# STM32VET6.net
KiCad netlist of a schematic drawn in Altium Designer
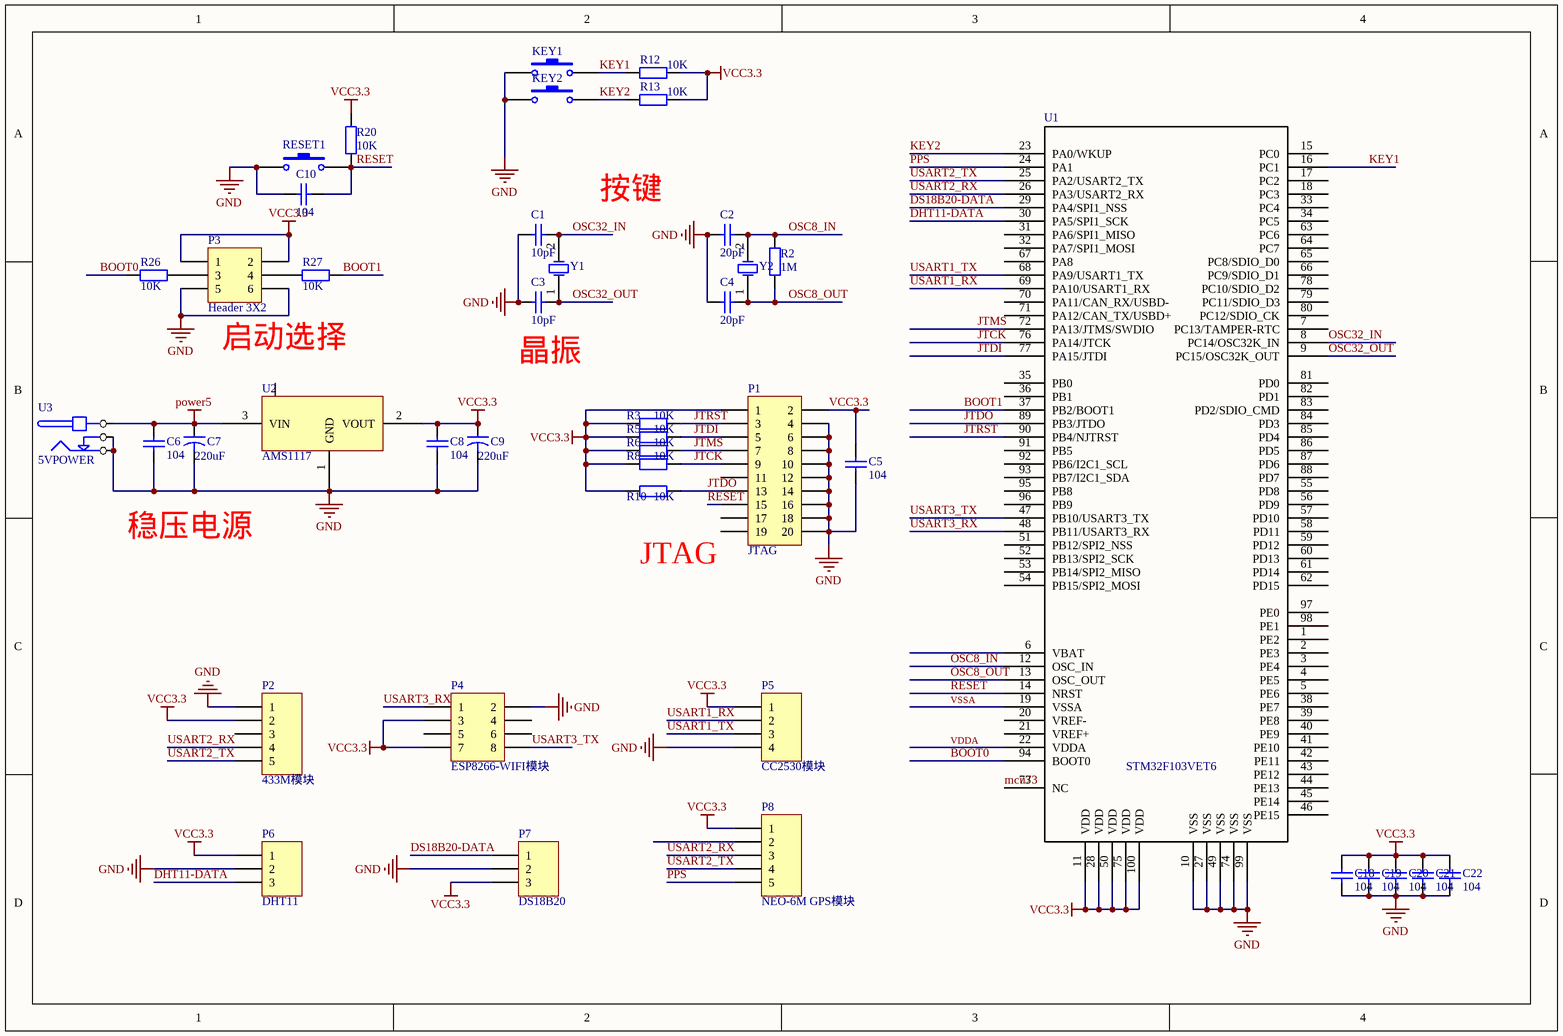
[diagram p0: STM32VET6.SchDoc]

(export (version "E")
  (design (tool "Eeschema 10.0.6"))
  (components
    (comp (ref "C1")
      (value "10pF")
      (footprint "0805")
      (description "Capacitor")
      (fields (field (name "Comment") "Cap") (field (name "PUBLISHER") "Altium Limited"))
      (libsource (lib "Miscellaneous Devices") (part "Cap"))
    )
    (comp (ref "C2")
      (value "20pF")
      (footprint "0805")
      (description "Capacitor")
      (fields (field (name "Comment") "Cap") (field (name "PUBLISHER") "Altium Limited"))
      (libsource (lib "Miscellaneous Devices") (part "Cap"))
    )
    (comp (ref "C3")
      (value "10pF")
      (footprint "0805")
      (description "Capacitor")
      (fields (field (name "Comment") "Cap") (field (name "PUBLISHER") "Altium Limited"))
      (libsource (lib "Miscellaneous Devices") (part "Cap"))
    )
    (comp (ref "C4")
      (value "20pF")
      (footprint "0805")
      (description "Capacitor")
      (fields (field (name "Comment") "Cap") (field (name "PUBLISHER") "Altium Limited"))
      (libsource (lib "Miscellaneous Devices") (part "Cap"))
    )
    (comp (ref "C5")
      (value "104")
      (footprint "0805")
      (description "Capacitor")
      (fields (field (name "Comment") "Cap") (field (name "PUBLISHER") "Altium Limited"))
      (libsource (lib "Miscellaneous Devices") (part "Cap"))
    )
    (comp (ref "C6")
      (value "104")
      (footprint "0805")
      (description "Capacitor")
      (fields (field (name "Comment") "Cap") (field (name "PUBLISHER") "Altium Limited"))
      (libsource (lib "Miscellaneous Devices") (part "Cap"))
    )
    (comp (ref "C7")
      (value "220uF")
      (footprint "非0805贴片电容")
      (description "Capacitor")
      (fields (field (name "Comment") "Cap2") (field (name "PUBLISHER") "Altium Limited"))
      (libsource (lib "Miscellaneous Devices") (part "Cap2"))
    )
    (comp (ref "C8")
      (value "104")
      (footprint "0805")
      (description "Capacitor")
      (fields (field (name "Comment") "Cap") (field (name "PUBLISHER") "Altium Limited"))
      (libsource (lib "Miscellaneous Devices") (part "Cap"))
    )
    (comp (ref "C9")
      (value "220uF")
      (footprint "非0805贴片电容")
      (description "Capacitor")
      (fields (field (name "Comment") "Cap2") (field (name "PUBLISHER") "Altium Limited"))
      (libsource (lib "Miscellaneous Devices") (part "Cap2"))
    )
    (comp (ref "C10")
      (value "104")
      (footprint "0805")
      (description "Capacitor")
      (fields (field (name "Comment") "Cap") (field (name "PUBLISHER") "Altium Limited"))
      (libsource (lib "Miscellaneous Devices") (part "Cap"))
    )
    (comp (ref "C18")
      (value "104")
      (footprint "0805")
      (description "Capacitor")
      (fields (field (name "Comment") "Cap") (field (name "PUBLISHER") "Altium Limited"))
      (libsource (lib "Miscellaneous Devices") (part "Cap"))
    )
    (comp (ref "C19")
      (value "104")
      (footprint "0805")
      (description "Capacitor")
      (fields (field (name "Comment") "Cap") (field (name "PUBLISHER") "Altium Limited"))
      (libsource (lib "Miscellaneous Devices") (part "Cap"))
    )
    (comp (ref "C20")
      (value "104")
      (footprint "0805")
      (description "Capacitor")
      (fields (field (name "Comment") "Cap") (field (name "PUBLISHER") "Altium Limited"))
      (libsource (lib "Miscellaneous Devices") (part "Cap"))
    )
    (comp (ref "C21")
      (value "104")
      (footprint "0805")
      (description "Capacitor")
      (fields (field (name "Comment") "Cap") (field (name "PUBLISHER") "Altium Limited"))
      (libsource (lib "Miscellaneous Devices") (part "Cap"))
    )
    (comp (ref "C22")
      (value "104")
      (footprint "0805")
      (description "Capacitor")
      (fields (field (name "Comment") "Cap") (field (name "PUBLISHER") "Altium Limited"))
      (libsource (lib "Miscellaneous Devices") (part "Cap"))
    )
    (comp (ref "KEY1")
      (value "SW-PB")
      (footprint "PUSHSW")
      (description "Switch")
      (fields (field (name "PUBLISHER") "Altium Limited"))
      (libsource (lib "gtm900") (part "SW-PB"))
    )
    (comp (ref "KEY2")
      (value "SW-PB")
      (footprint "PUSHSW")
      (description "Switch")
      (fields (field (name "PUBLISHER") "Altium Limited"))
      (libsource (lib "gtm900") (part "SW-PB"))
    )
    (comp (ref "P1")
      (value "JTAG")
      (footprint "HDR2X10")
      (description "Header, 10-Pin, Dual row")
      (fields (field (name "PUBLISHER") "Altium Limited"))
      (libsource (lib "Miscellaneous Connectors") (part "Header 10X2"))
    )
    (comp (ref "P2")
      (value "433M模块")
      (footprint "HDR1X5")
      (description "Header, 5-Pin")
      (fields (field (name "PUBLISHER") "Altium Limited"))
      (libsource (lib "Miscellaneous Connectors") (part "Header 5"))
    )
    (comp (ref "P3")
      (value "Header 3X2")
      (footprint "HDR2X3")
      (description "Header, 3-Pin, Dual row")
      (fields (field (name "PUBLISHER") "Altium Limited"))
      (libsource (lib "Miscellaneous Connectors") (part "Header 3X2"))
    )
    (comp (ref "P4")
      (value "ESP8266-WIFI模块")
      (footprint "HDR2X4")
      (description "Header, 4-Pin, Dual row")
      (fields (field (name "PUBLISHER") "Altium Limited"))
      (libsource (lib "Miscellaneous Connectors") (part "Header 4X2"))
    )
    (comp (ref "P5")
      (value "CC2530模块")
      (footprint "HDR1X4")
      (description "Header, 4-Pin")
      (fields (field (name "PUBLISHER") "Altium Limited"))
      (libsource (lib "Miscellaneous Connectors") (part "Header 4"))
    )
    (comp (ref "P6")
      (value "DHT11")
      (footprint "HDR1X3")
      (description "Header, 3-Pin")
      (fields (field (name "PUBLISHER") "Altium Limited"))
      (libsource (lib "Miscellaneous Connectors") (part "Header 3"))
    )
    (comp (ref "P7")
      (value "DS18B20")
      (footprint "HDR1X3")
      (description "Header, 3-Pin")
      (fields (field (name "PUBLISHER") "Altium Limited"))
      (libsource (lib "Miscellaneous Connectors") (part "Header 3"))
    )
    (comp (ref "P8")
      (value "NEO-6M GPS模块")
      (footprint "HDR1X5")
      (description "Header, 5-Pin")
      (fields (field (name "PUBLISHER") "Altium Limited"))
      (libsource (lib "Miscellaneous Connectors") (part "Header 5"))
    )
    (comp (ref "R2")
      (value "1M")
      (footprint "0805")
      (description "Resistor")
      (fields (field (name "Comment") "Res2") (field (name "PUBLISHER") "Altium Limited"))
      (libsource (lib "") (part "Res2_1"))
    )
    (comp (ref "R3")
      (value "10K")
      (footprint "0805")
      (description "Resistor")
      (fields (field (name "Comment") "Res2") (field (name "PUBLISHER") "Altium Limited"))
      (libsource (lib "Miscellaneous Devices") (part "Res2"))
    )
    (comp (ref "R5")
      (value "10K")
      (footprint "0805")
      (description "Resistor")
      (fields (field (name "Comment") "Res2") (field (name "PUBLISHER") "Altium Limited"))
      (libsource (lib "Miscellaneous Devices") (part "Res2"))
    )
    (comp (ref "R6")
      (value "10K")
      (footprint "0805")
      (description "Resistor")
      (fields (field (name "Comment") "Res2") (field (name "PUBLISHER") "Altium Limited"))
      (libsource (lib "Miscellaneous Devices") (part "Res2"))
    )
    (comp (ref "R8")
      (value "10K")
      (footprint "0805")
      (description "Resistor")
      (fields (field (name "Comment") "Res2") (field (name "PUBLISHER") "Altium Limited"))
      (libsource (lib "Miscellaneous Devices") (part "Res2"))
    )
    (comp (ref "R10")
      (value "10K")
      (footprint "0805")
      (description "Resistor")
      (fields (field (name "Comment") "Res2") (field (name "PUBLISHER") "Altium Limited"))
      (libsource (lib "Miscellaneous Devices") (part "Res2"))
    )
    (comp (ref "R12")
      (value "10K")
      (footprint "0805")
      (description "Resistor")
      (fields (field (name "Comment") "Res2") (field (name "PUBLISHER") "Altium Limited"))
      (libsource (lib "Miscellaneous Devices") (part "Res2"))
    )
    (comp (ref "R13")
      (value "10K")
      (footprint "0805")
      (description "Resistor")
      (fields (field (name "Comment") "Res2") (field (name "PUBLISHER") "Altium Limited"))
      (libsource (lib "Miscellaneous Devices") (part "Res2"))
    )
    (comp (ref "R20")
      (value "10K")
      (footprint "0805")
      (description "Resistor")
      (fields (field (name "Comment") "Res2") (field (name "PUBLISHER") "Altium Limited"))
      (libsource (lib "Miscellaneous Devices") (part "Res2"))
    )
    (comp (ref "R26")
      (value "10K")
      (footprint "0805")
      (description "Resistor")
      (fields (field (name "Comment") "Res2") (field (name "PUBLISHER") "Altium Limited"))
      (libsource (lib "") (part "Res2_2"))
    )
    (comp (ref "R27")
      (value "10K")
      (footprint "0805")
      (description "Resistor")
      (fields (field (name "Comment") "Res2") (field (name "PUBLISHER") "Altium Limited"))
      (libsource (lib "") (part "Res2_2"))
    )
    (comp (ref "RESET1")
      (value "SW-PB")
      (footprint "PUSHSW")
      (description "Switch")
      (fields (field (name "PUBLISHER") "Altium Limited"))
      (libsource (lib "gtm900") (part "SW-PB"))
    )
    (comp (ref "U1")
      (value "STM32F103VET6")
      (footprint "LQFP100")
      (libsource (lib "Schlib1") (part "STM32F103VET6"))
    )
    (comp (ref "U2") (value "AMS1117") (footprint "SPX1117M") (libsource (lib "SPX1117") (part "SPX1117")))
    (comp (ref "U3") (value "5VPOWER") (footprint "power3_1") (libsource (lib "插座") (part "9VPOWER")))
    (comp (ref "Y1")
      (value "XTAL")
      (footprint "SM8")
      (description "Crystal Oscillator")
      (fields (field (name "PUBLISHER") "Altium Limited"))
      (libsource (lib "Miscellaneous Devices") (part "XTAL"))
    )
    (comp (ref "Y2")
      (value "XTAL")
      (footprint "XTAL-2")
      (description "Crystal Oscillator")
      (fields (field (name "PUBLISHER") "Altium Limited"))
      (libsource (lib "Miscellaneous Devices") (part "XTAL"))
    )
  )
  (nets
    (net (code "1") (name "/BOOT0") (class "Default")
      (node (ref "R26") (pin "1") (pinfunction "1_1") (pintype "passive"))
      (node (ref "U1") (pin "94") (pinfunction "BOOT0_94") (pintype "passive"))
    )
    (net (code "2") (name "/BOOT1") (class "Default")
      (node (ref "R27") (pin "2") (pinfunction "2_2") (pintype "passive"))
      (node (ref "U1") (pin "37") (pinfunction "PB2/BOOT1_37") (pintype "passive"))
    )
    (net (code "3") (name "/DHT11-DATA") (class "Default")
      (node (ref "P6") (pin "3") (pinfunction "3_3") (pintype "passive"))
      (node (ref "U1") (pin "30") (pinfunction "PA5/SPI1_SCK_30") (pintype "passive"))
    )
    (net (code "4") (name "/DS18B20-DATA") (class "Default")
      (node (ref "P7") (pin "1") (pinfunction "1_1") (pintype "passive"))
      (node (ref "U1") (pin "29") (pinfunction "PA4/SPI1_NSS_29") (pintype "passive"))
    )
    (net (code "5") (name "/JTCK") (class "Default")
      (node (ref "P1") (pin "9") (pinfunction "9_9") (pintype "passive"))
      (node (ref "R8") (pin "1") (pinfunction "1_1") (pintype "passive"))
      (node (ref "U1") (pin "76") (pinfunction "PA14/JTCK_76") (pintype "passive"))
    )
    (net (code "6") (name "/JTDI") (class "Default")
      (node (ref "P1") (pin "5") (pinfunction "5_5") (pintype "passive"))
      (node (ref "R5") (pin "1") (pinfunction "1_1") (pintype "passive"))
      (node (ref "U1") (pin "77") (pinfunction "PA15/JTDI_77") (pintype "passive"))
    )
    (net (code "7") (name "/JTDO") (class "Default")
      (node (ref "P1") (pin "13") (pinfunction "13_13") (pintype "passive"))
      (node (ref "R10") (pin "1") (pinfunction "1_1") (pintype "passive"))
      (node (ref "U1") (pin "89") (pinfunction "PB3/JTDO_89") (pintype "passive"))
    )
    (net (code "8") (name "/JTMS") (class "Default")
      (node (ref "P1") (pin "7") (pinfunction "7_7") (pintype "passive"))
      (node (ref "R6") (pin "1") (pinfunction "1_1") (pintype "passive"))
      (node (ref "U1") (pin "72") (pinfunction "PA13/JTMS/SWDIO_72") (pintype "passive"))
    )
    (net (code "9") (name "/JTRST") (class "Default")
      (node (ref "P1") (pin "3") (pinfunction "3_3") (pintype "passive"))
      (node (ref "R3") (pin "1") (pinfunction "1_1") (pintype "passive"))
      (node (ref "U1") (pin "90") (pinfunction "PB4/NJTRST_90") (pintype "passive"))
    )
    (net (code "10") (name "/KEY1") (class "Default")
      (node (ref "KEY1") (pin "2") (pinfunction "2_2") (pintype "passive"))
      (node (ref "R12") (pin "2") (pinfunction "2_2") (pintype "passive"))
      (node (ref "U1") (pin "16") (pinfunction "PC1_16") (pintype "passive"))
    )
    (net (code "11") (name "/KEY2") (class "Default")
      (node (ref "KEY2") (pin "2") (pinfunction "2_2") (pintype "passive"))
      (node (ref "R13") (pin "2") (pinfunction "2_2") (pintype "passive"))
      (node (ref "U1") (pin "23") (pinfunction "PA0/WKUP_23") (pintype "passive"))
    )
    (net (code "12") (name "/OSC8_IN") (class "Default")
      (node (ref "C2") (pin "2") (pinfunction "2_2") (pintype "passive"))
      (node (ref "R2") (pin "2") (pinfunction "2_2") (pintype "passive"))
      (node (ref "U1") (pin "12") (pinfunction "OSC_IN_12") (pintype "passive"))
      (node (ref "Y2") (pin "2") (pinfunction "OSC2_2") (pintype "passive"))
    )
    (net (code "13") (name "/OSC8_OUT") (class "Default")
      (node (ref "C4") (pin "2") (pinfunction "2_2") (pintype "passive"))
      (node (ref "R2") (pin "1") (pinfunction "1_1") (pintype "passive"))
      (node (ref "U1") (pin "13") (pinfunction "OSC_OUT_13") (pintype "passive"))
      (node (ref "Y2") (pin "1") (pinfunction "OSC1_1") (pintype "passive"))
    )
    (net (code "14") (name "/OSC32_IN") (class "Default")
      (node (ref "C1") (pin "2") (pinfunction "2_2") (pintype "passive"))
      (node (ref "U1") (pin "8") (pinfunction "PC14/OSC32K_IN_8") (pintype "passive"))
      (node (ref "Y1") (pin "2") (pinfunction "OSC2_2") (pintype "passive"))
    )
    (net (code "15") (name "/OSC32_OUT") (class "Default")
      (node (ref "C3") (pin "2") (pinfunction "2_2") (pintype "passive"))
      (node (ref "U1") (pin "9") (pinfunction "PC15/OSC32K_OUT_9") (pintype "passive"))
      (node (ref "Y1") (pin "1") (pinfunction "OSC1_1") (pintype "passive"))
    )
    (net (code "16") (name "/PPS") (class "Default")
      (node (ref "P8") (pin "5") (pinfunction "5_5") (pintype "passive"))
      (node (ref "U1") (pin "24") (pinfunction "PA1_24") (pintype "passive"))
    )
    (net (code "17") (name "/RESET") (class "Default")
      (node (ref "C10") (pin "2") (pinfunction "2_2") (pintype "passive"))
      (node (ref "P1") (pin "15") (pinfunction "15_15") (pintype "passive"))
      (node (ref "R20") (pin "2") (pinfunction "2_2") (pintype "passive"))
      (node (ref "RESET1") (pin "1") (pinfunction "1_1") (pintype "passive"))
      (node (ref "U1") (pin "14") (pinfunction "NRST_14") (pintype "passive"))
    )
    (net (code "18") (name "/USART1_RX") (class "Default")
      (node (ref "P5") (pin "2") (pinfunction "2_2") (pintype "passive"))
      (node (ref "U1") (pin "69") (pinfunction "PA10/USART1_RX_69") (pintype "passive"))
    )
    (net (code "19") (name "/USART1_TX") (class "Default")
      (node (ref "P5") (pin "3") (pinfunction "3_3") (pintype "passive"))
      (node (ref "U1") (pin "68") (pinfunction "PA9/USART1_TX_68") (pintype "passive"))
    )
    (net (code "20") (name "/USART2_RX") (class "Default")
      (node (ref "P2") (pin "4") (pinfunction "4_4") (pintype "passive"))
      (node (ref "P8") (pin "3") (pinfunction "3_3") (pintype "passive"))
      (node (ref "U1") (pin "26") (pinfunction "PA3/USART2_RX_26") (pintype "passive"))
    )
    (net (code "21") (name "/USART2_TX") (class "Default")
      (node (ref "P2") (pin "5") (pinfunction "5_5") (pintype "passive"))
      (node (ref "P8") (pin "4") (pinfunction "4_4") (pintype "passive"))
      (node (ref "U1") (pin "25") (pinfunction "PA2/USART2_TX_25") (pintype "passive"))
    )
    (net (code "22") (name "/USART3_RX") (class "Default")
      (node (ref "P4") (pin "1") (pinfunction "1_1") (pintype "passive"))
      (node (ref "U1") (pin "48") (pinfunction "PB11/USART3_RX_48") (pintype "passive"))
    )
    (net (code "23") (name "/USART3_TX") (class "Default")
      (node (ref "P4") (pin "8") (pinfunction "8_8") (pintype "passive"))
      (node (ref "U1") (pin "47") (pinfunction "PB10/USART3_TX_47") (pintype "passive"))
    )
    (net (code "24") (name "/VDDA") (class "Default")
      (node (ref "U1") (pin "22") (pinfunction "VDDA_22") (pintype "passive"))
    )
    (net (code "25") (name "/VSSA") (class "Default")
      (node (ref "U1") (pin "19") (pinfunction "VSSA_19") (pintype "passive"))
    )
    (net (code "26") (name "/mcu73") (class "Default")
      (node (ref "U1") (pin "73") (pinfunction "NC_73") (pintype "passive"))
    )
    (net (code "27") (name "GND") (class "Default")
      (node (ref "C1") (pin "1") (pinfunction "1_1") (pintype "passive"))
      (node (ref "C10") (pin "1") (pinfunction "1_1") (pintype "passive"))
      (node (ref "C18") (pin "1") (pinfunction "1_1") (pintype "passive"))
      (node (ref "C19") (pin "1") (pinfunction "1_1") (pintype "passive"))
      (node (ref "C2") (pin "1") (pinfunction "1_1") (pintype "passive"))
      (node (ref "C20") (pin "1") (pinfunction "1_1") (pintype "passive"))
      (node (ref "C21") (pin "1") (pinfunction "1_1") (pintype "passive"))
      (node (ref "C22") (pin "1") (pinfunction "1_1") (pintype "passive"))
      (node (ref "C3") (pin "1") (pinfunction "1_1") (pintype "passive"))
      (node (ref "C4") (pin "1") (pinfunction "1_1") (pintype "passive"))
      (node (ref "C5") (pin "1") (pinfunction "1_1") (pintype "passive"))
      (node (ref "C6") (pin "1") (pinfunction "1_1") (pintype "passive"))
      (node (ref "C7") (pin "2") (pinfunction "2_2") (pintype "passive"))
      (node (ref "C8") (pin "1") (pinfunction "1_1") (pintype "passive"))
      (node (ref "C9") (pin "2") (pinfunction "2_2") (pintype "passive"))
      (node (ref "KEY1") (pin "1") (pinfunction "1_1") (pintype "passive"))
      (node (ref "KEY2") (pin "1") (pinfunction "1_1") (pintype "passive"))
      (node (ref "P1") (pin "10") (pinfunction "10_10") (pintype "passive"))
      (node (ref "P1") (pin "12") (pinfunction "12_12") (pintype "passive"))
      (node (ref "P1") (pin "14") (pinfunction "14_14") (pintype "passive"))
      (node (ref "P1") (pin "16") (pinfunction "16_16") (pintype "passive"))
      (node (ref "P1") (pin "18") (pinfunction "18_18") (pintype "passive"))
      (node (ref "P1") (pin "20") (pinfunction "20_20") (pintype "passive"))
      (node (ref "P1") (pin "4") (pinfunction "4_4") (pintype "passive"))
      (node (ref "P1") (pin "6") (pinfunction "6_6") (pintype "passive"))
      (node (ref "P1") (pin "8") (pinfunction "8_8") (pintype "passive"))
      (node (ref "P2") (pin "1") (pinfunction "1_1") (pintype "passive"))
      (node (ref "P3") (pin "5") (pinfunction "5_5") (pintype "passive"))
      (node (ref "P3") (pin "6") (pinfunction "6_6") (pintype "passive"))
      (node (ref "P4") (pin "2") (pinfunction "2_2") (pintype "passive"))
      (node (ref "P5") (pin "4") (pinfunction "4_4") (pintype "passive"))
      (node (ref "P6") (pin "2") (pinfunction "2_2") (pintype "passive"))
      (node (ref "P7") (pin "2") (pinfunction "2_2") (pintype "passive"))
      (node (ref "RESET1") (pin "2") (pinfunction "2_2") (pintype "passive"))
      (node (ref "U1") (pin "10") (pinfunction "VSS_10") (pintype "passive"))
      (node (ref "U1") (pin "27") (pinfunction "VSS_27") (pintype "passive"))
      (node (ref "U1") (pin "49") (pinfunction "VSS_49") (pintype "passive"))
      (node (ref "U1") (pin "74") (pinfunction "VSS_74") (pintype "passive"))
      (node (ref "U1") (pin "99") (pinfunction "VSS_99") (pintype "passive"))
      (node (ref "U2") (pin "1") (pinfunction "GND_1") (pintype "passive"))
      (node (ref "U3") (pin "1") (pintype "passive"))
      (node (ref "U3") (pin "2") (pintype "passive"))
    )
    (net (code "28") (name "Net-(P3-Pad3)") (class "Default")
      (node (ref "P3") (pin "3") (pinfunction "3_3") (pintype "passive"))
      (node (ref "R26") (pin "2") (pinfunction "2_2") (pintype "passive"))
    )
    (net (code "29") (name "Net-(P3-Pad4)") (class "Default")
      (node (ref "P3") (pin "4") (pinfunction "4_4") (pintype "passive"))
      (node (ref "R27") (pin "1") (pinfunction "1_1") (pintype "passive"))
    )
    (net (code "30") (name "VCC3.3") (class "Default")
      (node (ref "C18") (pin "2") (pinfunction "2_2") (pintype "passive"))
      (node (ref "C19") (pin "2") (pinfunction "2_2") (pintype "passive"))
      (node (ref "C20") (pin "2") (pinfunction "2_2") (pintype "passive"))
      (node (ref "C21") (pin "2") (pinfunction "2_2") (pintype "passive"))
      (node (ref "C22") (pin "2") (pinfunction "2_2") (pintype "passive"))
      (node (ref "C5") (pin "2") (pinfunction "2_2") (pintype "passive"))
      (node (ref "C8") (pin "2") (pinfunction "2_2") (pintype "passive"))
      (node (ref "C9") (pin "1") (pinfunction "1_1") (pintype "passive"))
      (node (ref "P1") (pin "1") (pinfunction "1_1") (pintype "passive"))
      (node (ref "P1") (pin "2") (pinfunction "2_2") (pintype "passive"))
      (node (ref "P2") (pin "2") (pinfunction "2_2") (pintype "passive"))
      (node (ref "P3") (pin "1") (pinfunction "1_1") (pintype "passive"))
      (node (ref "P3") (pin "2") (pinfunction "2_2") (pintype "passive"))
      (node (ref "P4") (pin "3") (pinfunction "3_3") (pintype "passive"))
      (node (ref "P4") (pin "7") (pinfunction "7_7") (pintype "passive"))
      (node (ref "P5") (pin "1") (pinfunction "1_1") (pintype "passive"))
      (node (ref "P6") (pin "1") (pinfunction "1_1") (pintype "passive"))
      (node (ref "P7") (pin "3") (pinfunction "3_3") (pintype "passive"))
      (node (ref "P8") (pin "1") (pinfunction "1_1") (pintype "passive"))
      (node (ref "R10") (pin "2") (pinfunction "2_2") (pintype "passive"))
      (node (ref "R12") (pin "1") (pinfunction "1_1") (pintype "passive"))
      (node (ref "R13") (pin "1") (pinfunction "1_1") (pintype "passive"))
      (node (ref "R20") (pin "1") (pinfunction "1_1") (pintype "passive"))
      (node (ref "R3") (pin "2") (pinfunction "2_2") (pintype "passive"))
      (node (ref "R5") (pin "2") (pinfunction "2_2") (pintype "passive"))
      (node (ref "R6") (pin "2") (pinfunction "2_2") (pintype "passive"))
      (node (ref "R8") (pin "2") (pinfunction "2_2") (pintype "passive"))
      (node (ref "U1") (pin "100") (pinfunction "VDD_100") (pintype "passive"))
      (node (ref "U1") (pin "11") (pinfunction "VDD_11") (pintype "passive"))
      (node (ref "U1") (pin "28") (pinfunction "VDD_28") (pintype "passive"))
      (node (ref "U1") (pin "50") (pinfunction "VDD_50") (pintype "passive"))
      (node (ref "U1") (pin "75") (pinfunction "VDD_75") (pintype "passive"))
      (node (ref "U2") (pin "2") (pinfunction "VOUT_2") (pintype "passive"))
    )
    (net (code "31") (name "power5") (class "Default")
      (node (ref "C6") (pin "2") (pinfunction "2_2") (pintype "passive"))
      (node (ref "C7") (pin "1") (pinfunction "1_1") (pintype "passive"))
      (node (ref "U2") (pin "3") (pinfunction "VIN_3") (pintype "passive"))
      (node (ref "U3") (pin "3") (pintype "passive"))
    )
    (net (code "32") (name "unconnected-(P1-Pad11)") (class "Default")
      (node (ref "P1") (pin "11") (pinfunction "11_11") (pintype "passive"))
    )
    (net (code "33") (name "unconnected-(P1-Pad17)") (class "Default")
      (node (ref "P1") (pin "17") (pinfunction "17_17") (pintype "passive"))
    )
    (net (code "34") (name "unconnected-(P1-Pad19)") (class "Default")
      (node (ref "P1") (pin "19") (pinfunction "19_19") (pintype "passive"))
    )
    (net (code "35") (name "unconnected-(P2-Pad3)") (class "Default")
      (node (ref "P2") (pin "3") (pinfunction "3_3") (pintype "passive"))
    )
    (net (code "36") (name "unconnected-(P4-Pad4)") (class "Default")
      (node (ref "P4") (pin "4") (pinfunction "4_4") (pintype "passive"))
    )
    (net (code "37") (name "unconnected-(P4-Pad5)") (class "Default")
      (node (ref "P4") (pin "5") (pinfunction "5_5") (pintype "passive"))
    )
    (net (code "38") (name "unconnected-(P4-Pad6)") (class "Default")
      (node (ref "P4") (pin "6") (pinfunction "6_6") (pintype "passive"))
    )
    (net (code "39") (name "unconnected-(P8-Pad2)") (class "Default")
      (node (ref "P8") (pin "2") (pinfunction "2_2") (pintype "passive"))
    )
    (net (code "40") (name "unconnected-(U1-PA6{slash}SPI1_MISO-Pad31)") (class "Default")
      (node (ref "U1") (pin "31") (pinfunction "PA6/SPI1_MISO_31") (pintype "passive"))
    )
    (net (code "41") (name "unconnected-(U1-PA7{slash}SPI1_MOSI-Pad32)") (class "Default")
      (node (ref "U1") (pin "32") (pinfunction "PA7/SPI1_MOSI_32") (pintype "passive"))
    )
    (net (code "42") (name "unconnected-(U1-PA8-Pad67)") (class "Default")
      (node (ref "U1") (pin "67") (pinfunction "PA8_67") (pintype "passive"))
    )
    (net (code "43") (name "unconnected-(U1-PA11{slash}CAN_RX{slash}USBD--Pad70)") (class "Default")
      (node (ref "U1") (pin "70") (pinfunction "PA11/CAN_RX/USBD-_70") (pintype "passive"))
    )
    (net (code "44") (name "unconnected-(U1-PA12{slash}CAN_TX{slash}USBD+-Pad71)") (class "Default")
      (node (ref "U1") (pin "71") (pinfunction "PA12/CAN_TX/USBD+_71") (pintype "passive"))
    )
    (net (code "45") (name "unconnected-(U1-PB0-Pad35)") (class "Default")
      (node (ref "U1") (pin "35") (pinfunction "PB0_35") (pintype "passive"))
    )
    (net (code "46") (name "unconnected-(U1-PB1-Pad36)") (class "Default")
      (node (ref "U1") (pin "36") (pinfunction "PB1_36") (pintype "passive"))
    )
    (net (code "47") (name "unconnected-(U1-PB5-Pad91)") (class "Default")
      (node (ref "U1") (pin "91") (pinfunction "PB5_91") (pintype "passive"))
    )
    (net (code "48") (name "unconnected-(U1-PB6{slash}I2C1_SCL-Pad92)") (class "Default")
      (node (ref "U1") (pin "92") (pinfunction "PB6/I2C1_SCL_92") (pintype "passive"))
    )
    (net (code "49") (name "unconnected-(U1-PB7{slash}I2C1_SDA-Pad93)") (class "Default")
      (node (ref "U1") (pin "93") (pinfunction "PB7/I2C1_SDA_93") (pintype "passive"))
    )
    (net (code "50") (name "unconnected-(U1-PB8-Pad95)") (class "Default")
      (node (ref "U1") (pin "95") (pinfunction "PB8_95") (pintype "passive"))
    )
    (net (code "51") (name "unconnected-(U1-PB9-Pad96)") (class "Default")
      (node (ref "U1") (pin "96") (pinfunction "PB9_96") (pintype "passive"))
    )
    (net (code "52") (name "unconnected-(U1-PB12{slash}SPI2_NSS-Pad51)") (class "Default")
      (node (ref "U1") (pin "51") (pinfunction "PB12/SPI2_NSS_51") (pintype "passive"))
    )
    (net (code "53") (name "unconnected-(U1-PB13{slash}SPI2_SCK-Pad52)") (class "Default")
      (node (ref "U1") (pin "52") (pinfunction "PB13/SPI2_SCK_52") (pintype "passive"))
    )
    (net (code "54") (name "unconnected-(U1-PB14{slash}SPI2_MISO-Pad53)") (class "Default")
      (node (ref "U1") (pin "53") (pinfunction "PB14/SPI2_MISO_53") (pintype "passive"))
    )
    (net (code "55") (name "unconnected-(U1-PB15{slash}SPI2_MOSI-Pad54)") (class "Default")
      (node (ref "U1") (pin "54") (pinfunction "PB15/SPI2_MOSI_54") (pintype "passive"))
    )
    (net (code "56") (name "unconnected-(U1-PC0-Pad15)") (class "Default")
      (node (ref "U1") (pin "15") (pinfunction "PC0_15") (pintype "passive"))
    )
    (net (code "57") (name "unconnected-(U1-PC2-Pad17)") (class "Default")
      (node (ref "U1") (pin "17") (pinfunction "PC2_17") (pintype "passive"))
    )
    (net (code "58") (name "unconnected-(U1-PC3-Pad18)") (class "Default")
      (node (ref "U1") (pin "18") (pinfunction "PC3_18") (pintype "passive"))
    )
    (net (code "59") (name "unconnected-(U1-PC4-Pad33)") (class "Default")
      (node (ref "U1") (pin "33") (pinfunction "PC4_33") (pintype "passive"))
    )
    (net (code "60") (name "unconnected-(U1-PC5-Pad34)") (class "Default")
      (node (ref "U1") (pin "34") (pinfunction "PC5_34") (pintype "passive"))
    )
    (net (code "61") (name "unconnected-(U1-PC6-Pad63)") (class "Default")
      (node (ref "U1") (pin "63") (pinfunction "PC6_63") (pintype "passive"))
    )
    (net (code "62") (name "unconnected-(U1-PC7-Pad64)") (class "Default")
      (node (ref "U1") (pin "64") (pinfunction "PC7_64") (pintype "passive"))
    )
    (net (code "63") (name "unconnected-(U1-PC8{slash}SDIO_D0-Pad65)") (class "Default")
      (node (ref "U1") (pin "65") (pinfunction "PC8/SDIO_D0_65") (pintype "passive"))
    )
    (net (code "64") (name "unconnected-(U1-PC9{slash}SDIO_D1-Pad66)") (class "Default")
      (node (ref "U1") (pin "66") (pinfunction "PC9/SDIO_D1_66") (pintype "passive"))
    )
    (net (code "65") (name "unconnected-(U1-PC10{slash}SDIO_D2-Pad78)") (class "Default")
      (node (ref "U1") (pin "78") (pinfunction "PC10/SDIO_D2_78") (pintype "passive"))
    )
    (net (code "66") (name "unconnected-(U1-PC11{slash}SDIO_D3-Pad79)") (class "Default")
      (node (ref "U1") (pin "79") (pinfunction "PC11/SDIO_D3_79") (pintype "passive"))
    )
    (net (code "67") (name "unconnected-(U1-PC12{slash}SDIO_CK-Pad80)") (class "Default")
      (node (ref "U1") (pin "80") (pinfunction "PC12/SDIO_CK_80") (pintype "passive"))
    )
    (net (code "68") (name "unconnected-(U1-PC13{slash}TAMPER-RTC-Pad7)") (class "Default")
      (node (ref "U1") (pin "7") (pinfunction "PC13/TAMPER-RTC_7") (pintype "passive"))
    )
    (net (code "69") (name "unconnected-(U1-PD0-Pad81)") (class "Default")
      (node (ref "U1") (pin "81") (pinfunction "PD0_81") (pintype "passive"))
    )
    (net (code "70") (name "unconnected-(U1-PD1-Pad82)") (class "Default")
      (node (ref "U1") (pin "82") (pinfunction "PD1_82") (pintype "passive"))
    )
    (net (code "71") (name "unconnected-(U1-PD2{slash}SDIO_CMD-Pad83)") (class "Default")
      (node (ref "U1") (pin "83") (pinfunction "PD2/SDIO_CMD_83") (pintype "passive"))
    )
    (net (code "72") (name "unconnected-(U1-PD3-Pad84)") (class "Default")
      (node (ref "U1") (pin "84") (pinfunction "PD3_84") (pintype "passive"))
    )
    (net (code "73") (name "unconnected-(U1-PD4-Pad85)") (class "Default")
      (node (ref "U1") (pin "85") (pinfunction "PD4_85") (pintype "passive"))
    )
    (net (code "74") (name "unconnected-(U1-PD5-Pad86)") (class "Default")
      (node (ref "U1") (pin "86") (pinfunction "PD5_86") (pintype "passive"))
    )
    (net (code "75") (name "unconnected-(U1-PD6-Pad87)") (class "Default")
      (node (ref "U1") (pin "87") (pinfunction "PD6_87") (pintype "passive"))
    )
    (net (code "76") (name "unconnected-(U1-PD7-Pad88)") (class "Default")
      (node (ref "U1") (pin "88") (pinfunction "PD7_88") (pintype "passive"))
    )
    (net (code "77") (name "unconnected-(U1-PD8-Pad55)") (class "Default")
      (node (ref "U1") (pin "55") (pinfunction "PD8_55") (pintype "passive"))
    )
    (net (code "78") (name "unconnected-(U1-PD9-Pad56)") (class "Default")
      (node (ref "U1") (pin "56") (pinfunction "PD9_56") (pintype "passive"))
    )
    (net (code "79") (name "unconnected-(U1-PD10-Pad57)") (class "Default")
      (node (ref "U1") (pin "57") (pinfunction "PD10_57") (pintype "passive"))
    )
    (net (code "80") (name "unconnected-(U1-PD11-Pad58)") (class "Default")
      (node (ref "U1") (pin "58") (pinfunction "PD11_58") (pintype "passive"))
    )
    (net (code "81") (name "unconnected-(U1-PD12-Pad59)") (class "Default")
      (node (ref "U1") (pin "59") (pinfunction "PD12_59") (pintype "passive"))
    )
    (net (code "82") (name "unconnected-(U1-PD13-Pad60)") (class "Default")
      (node (ref "U1") (pin "60") (pinfunction "PD13_60") (pintype "passive"))
    )
    (net (code "83") (name "unconnected-(U1-PD14-Pad61)") (class "Default")
      (node (ref "U1") (pin "61") (pinfunction "PD14_61") (pintype "passive"))
    )
    (net (code "84") (name "unconnected-(U1-PD15-Pad62)") (class "Default")
      (node (ref "U1") (pin "62") (pinfunction "PD15_62") (pintype "passive"))
    )
    (net (code "85") (name "unconnected-(U1-PE0-Pad97)") (class "Default")
      (node (ref "U1") (pin "97") (pinfunction "PE0_97") (pintype "passive"))
    )
    (net (code "86") (name "unconnected-(U1-PE1-Pad98)") (class "Default")
      (node (ref "U1") (pin "98") (pinfunction "PE1_98") (pintype "passive"))
    )
    (net (code "87") (name "unconnected-(U1-PE2-Pad1)") (class "Default")
      (node (ref "U1") (pin "1") (pinfunction "PE2_1") (pintype "passive"))
    )
    (net (code "88") (name "unconnected-(U1-PE3-Pad2)") (class "Default")
      (node (ref "U1") (pin "2") (pinfunction "PE3_2") (pintype "passive"))
    )
    (net (code "89") (name "unconnected-(U1-PE4-Pad3)") (class "Default")
      (node (ref "U1") (pin "3") (pinfunction "PE4_3") (pintype "passive"))
    )
    (net (code "90") (name "unconnected-(U1-PE5-Pad4)") (class "Default")
      (node (ref "U1") (pin "4") (pinfunction "PE5_4") (pintype "passive"))
    )
    (net (code "91") (name "unconnected-(U1-PE6-Pad5)") (class "Default")
      (node (ref "U1") (pin "5") (pinfunction "PE6_5") (pintype "passive"))
    )
    (net (code "92") (name "unconnected-(U1-PE7-Pad38)") (class "Default")
      (node (ref "U1") (pin "38") (pinfunction "PE7_38") (pintype "passive"))
    )
    (net (code "93") (name "unconnected-(U1-PE8-Pad39)") (class "Default")
      (node (ref "U1") (pin "39") (pinfunction "PE8_39") (pintype "passive"))
    )
    (net (code "94") (name "unconnected-(U1-PE9-Pad40)") (class "Default")
      (node (ref "U1") (pin "40") (pinfunction "PE9_40") (pintype "passive"))
    )
    (net (code "95") (name "unconnected-(U1-PE10-Pad41)") (class "Default")
      (node (ref "U1") (pin "41") (pinfunction "PE10_41") (pintype "passive"))
    )
    (net (code "96") (name "unconnected-(U1-PE11-Pad42)") (class "Default")
      (node (ref "U1") (pin "42") (pinfunction "PE11_42") (pintype "passive"))
    )
    (net (code "97") (name "unconnected-(U1-PE12-Pad43)") (class "Default")
      (node (ref "U1") (pin "43") (pinfunction "PE12_43") (pintype "passive"))
    )
    (net (code "98") (name "unconnected-(U1-PE13-Pad44)") (class "Default")
      (node (ref "U1") (pin "44") (pinfunction "PE13_44") (pintype "passive"))
    )
    (net (code "99") (name "unconnected-(U1-PE14-Pad45)") (class "Default")
      (node (ref "U1") (pin "45") (pinfunction "PE14_45") (pintype "passive"))
    )
    (net (code "100") (name "unconnected-(U1-PE15-Pad46)") (class "Default")
      (node (ref "U1") (pin "46") (pinfunction "PE15_46") (pintype "passive"))
    )
    (net (code "101") (name "unconnected-(U1-VBAT-Pad6)") (class "Default")
      (node (ref "U1") (pin "6") (pinfunction "VBAT_6") (pintype "passive"))
    )
    (net (code "102") (name "unconnected-(U1-VREF+-Pad21)") (class "Default")
      (node (ref "U1") (pin "21") (pinfunction "VREF+_21") (pintype "passive"))
    )
    (net (code "103") (name "unconnected-(U1-VREF--Pad20)") (class "Default")
      (node (ref "U1") (pin "20") (pinfunction "VREF-_20") (pintype "passive"))
    )
  )
)
